# Nano_pi.net
KiCad netlist of a schematic drawn in Altium Designer
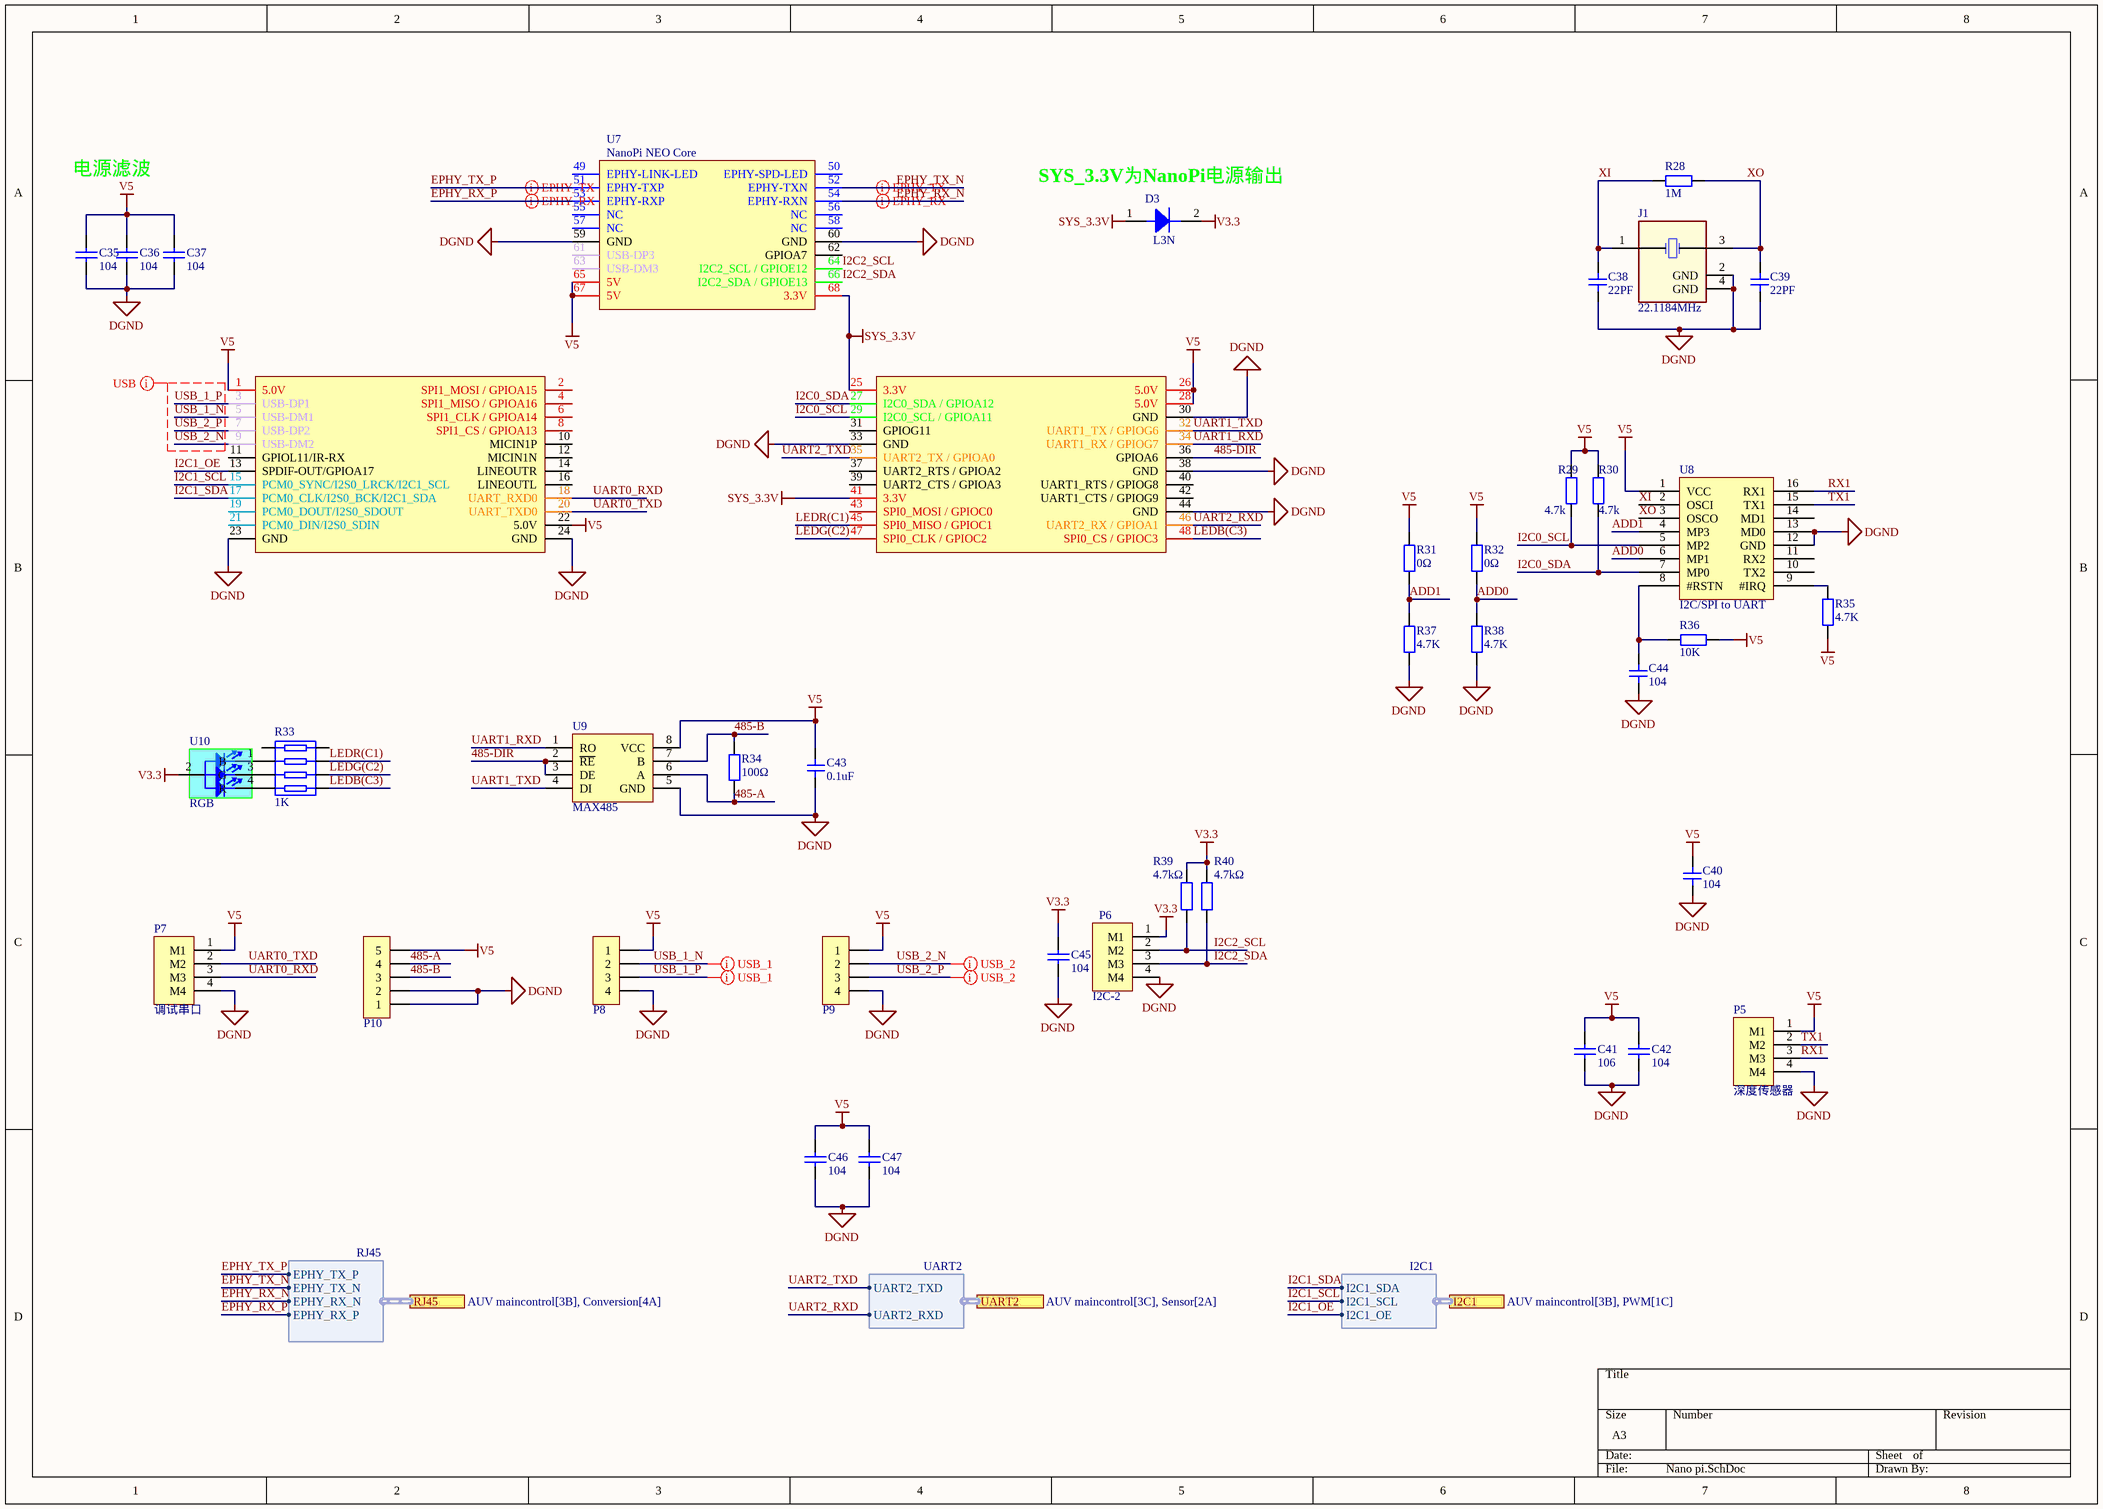
[diagram p0: Nano pi.SchDoc]

(export (version "E")
  (design (tool "Eeschema 10.0.6"))
  (components
    (comp (ref "C35")
      (value "104")
      (footprint "0603_C")
      (description "贴片电容")
      (libsource (lib "SFerret") (part "SMT_Cap"))
    )
    (comp (ref "C36")
      (value "104")
      (footprint "0603_C")
      (description "贴片电容")
      (libsource (lib "SFerret") (part "SMT_Cap"))
    )
    (comp (ref "C37")
      (value "104")
      (footprint "0603_C")
      (description "贴片电容")
      (libsource (lib "SFerret") (part "SMT_Cap"))
    )
    (comp (ref "C38")
      (value "22PF")
      (footprint "0603_C")
      (description "无极贴片电容")
      (libsource (lib "集大电协1.5") (part "Cap1"))
    )
    (comp (ref "C39")
      (value "22PF")
      (footprint "0603_C")
      (description "无极贴片电容")
      (libsource (lib "集大电协1.5") (part "Cap1"))
    )
    (comp (ref "C40")
      (value "104")
      (footprint "0603_C")
      (description "无极贴片电容")
      (libsource (lib "集大电协1.5") (part "Cap1"))
    )
    (comp (ref "C41")
      (value "106")
      (footprint "0603_C")
      (description "贴片电容")
      (libsource (lib "SFerret") (part "SMT_Cap"))
    )
    (comp (ref "C42")
      (value "104")
      (footprint "0603_C")
      (description "贴片电容")
      (libsource (lib "SFerret") (part "SMT_Cap"))
    )
    (comp (ref "C43")
      (value "0.1uF")
      (footprint "0603_C")
      (description "无极贴片电容")
      (libsource (lib "集大电协1.5") (part "Cap1"))
    )
    (comp (ref "C44")
      (value "104")
      (footprint "0603_C")
      (description "无极贴片电容")
      (libsource (lib "集大电协1.5") (part "Cap1"))
    )
    (comp (ref "C45")
      (value "104")
      (footprint "0603_C")
      (description "贴片电容")
      (libsource (lib "SFerret") (part "SMT_Cap"))
    )
    (comp (ref "C46")
      (value "104")
      (footprint "0603_C")
      (description "贴片电容")
      (libsource (lib "SFerret") (part "SMT_Cap"))
    )
    (comp (ref "C47")
      (value "104")
      (footprint "0603_C")
      (description "贴片电容")
      (libsource (lib "SFerret") (part "SMT_Cap"))
    )
    (comp (ref "D3")
      (value "L3N")
      (footprint "SOD-123")
      (description "二极管30V/2A")
      (libsource (lib "集大电协1.5") (part "Diode"))
    )
    (comp (ref "J1")
      (value "22.1184MHz")
      (footprint "SMD-3225_4P")
      (libsource (lib "SFerret") (part "Oscillator_SMT_4P"))
    )
    (comp (ref "P5")
      (value "深度传感器")
      (footprint "MX1.25S-4P")
      (description "4PIN")
      (libsource (lib "集大电协1.5") (part "接线端子-4PIN"))
    )
    (comp (ref "P6")
      (value "I2C-2")
      (footprint "MX1.25S-4P")
      (description "4PIN")
      (libsource (lib "集大电协1.5") (part "接线端子-4PIN"))
    )
    (comp (ref "P7")
      (value "调试串口")
      (footprint "MX1.25S-4P")
      (description "4PIN")
      (libsource (lib "集大电协1.5") (part "接线端子-4PIN"))
    )
    (comp (ref "P8")
      (value "HDR-1X4")
      (footprint "PH2.0-LS-4P")
      (description "4P接插件")
      (libsource (lib "5.3 - 接插件-脚距2.0") (part "Header 4"))
    )
    (comp (ref "P9")
      (value "HDR-1X4")
      (footprint "PH2.0-LS-4P")
      (description "4P接插件")
      (libsource (lib "5.3 - 接插件-脚距2.0") (part "Header 4"))
    )
    (comp (ref "P10")
      (value "HDR-1X5")
      (footprint "PH2.0-LS-5P")
      (description "5P接插件")
      (libsource (lib "5.3 - 接插件-脚距2.0") (part "Header 5"))
    )
    (comp (ref "R28")
      (value "1M")
      (footprint "0603R")
      (description "电阻")
      (libsource (lib "集大电协1.5") (part "Res"))
    )
    (comp (ref "R29")
      (value "4.7k")
      (footprint "0603R")
      (description "电阻")
      (libsource (lib "集大电协1.5") (part "Res"))
    )
    (comp (ref "R30")
      (value "4.7k")
      (footprint "0603R")
      (description "电阻")
      (libsource (lib "集大电协1.5") (part "Res"))
    )
    (comp (ref "R31")
      (value "0Ω")
      (footprint "0603R")
      (description "电阻")
      (libsource (lib "集大电协1.5") (part "Res"))
    )
    (comp (ref "R32")
      (value "0Ω")
      (footprint "0603R")
      (description "电阻")
      (libsource (lib "集大电协1.5") (part "Res"))
    )
    (comp (ref "R33")
      (value "1K")
      (footprint "res-4")
      (description "排阻")
      (libsource (lib "集大电协1.5") (part "Res-4"))
    )
    (comp (ref "R34")
      (value "100Ω")
      (footprint "0603R")
      (description "电阻")
      (libsource (lib "集大电协1.5") (part "Res"))
    )
    (comp (ref "R35")
      (value "4.7K")
      (footprint "0603R")
      (description "电阻")
      (libsource (lib "集大电协1.5") (part "Res"))
    )
    (comp (ref "R36")
      (value "10K")
      (footprint "0603R")
      (description "电阻")
      (libsource (lib "集大电协1.5") (part "Res"))
    )
    (comp (ref "R37")
      (value "4.7K")
      (footprint "0603R")
      (description "电阻")
      (libsource (lib "集大电协1.5") (part "Res"))
    )
    (comp (ref "R38")
      (value "4.7K")
      (footprint "0603R")
      (description "电阻")
      (libsource (lib "集大电协1.5") (part "Res"))
    )
    (comp (ref "R39")
      (value "4.7kΩ")
      (footprint "0603_R")
      (description "贴片电阻")
      (libsource (lib "SFerret") (part "SMT_Res"))
    )
    (comp (ref "R40")
      (value "4.7kΩ")
      (footprint "0603_R")
      (description "贴片电阻")
      (libsource (lib "SFerret") (part "SMT_Res"))
    )
    (comp (ref "U7")
      (value "NanoPi NEO Core")
      (footprint "NanoPi NEO Core(无引脚名)")
      (libsource (lib "集大电协1.5") (part "NanoPi NEO Core"))
    )
    (comp (ref "U8")
      (value "I2C/SPI to UART")
      (footprint "SOP65P780X195-16N")
      (libsource (lib "SFerret") (part "WK2132-ISSG"))
    )
    (comp (ref "U9") (value "MAX485") (footprint "SOP-8") (libsource (lib "集大电协1.5") (part "MAX485")))
    (comp (ref "U10") (value "RGB") (footprint "RGB-3528") (libsource (lib "集大电协1.1.2") (part "RGB")))
  )
  (nets
    (net (code "4") (name "/485-A") (class "Default")
      (node (ref "P10") (pin "4") (pinfunction "4_4") (pintype "passive"))
      (node (ref "R34") (pin "1") (pinfunction "1_1") (pintype "passive"))
      (node (ref "U9") (pin "6") (pinfunction "A_6") (pintype "passive"))
    )
    (net (code "5") (name "/485-B") (class "Default")
      (node (ref "P10") (pin "3") (pinfunction "3_3") (pintype "passive"))
      (node (ref "R34") (pin "2") (pinfunction "2_2") (pintype "passive"))
      (node (ref "U9") (pin "7") (pinfunction "B_7") (pintype "passive"))
    )
    (net (code "6") (name "/485-DIR") (class "Default")
      (node (ref "U7") (pin "36") (pinfunction "GPIOA6_36") (pintype "passive"))
      (node (ref "U9") (pin "2") (pinfunction "~{RE}_2") (pintype "passive"))
      (node (ref "U9") (pin "3") (pinfunction "DE_3") (pintype "passive"))
    )
    (net (code "8") (name "/ADD0") (class "Default")
      (node (ref "R32") (pin "1") (pinfunction "1_1") (pintype "passive"))
      (node (ref "R38") (pin "2") (pinfunction "2_2") (pintype "passive"))
      (node (ref "U8") (pin "6") (pinfunction "MP1_6") (pintype "passive"))
    )
    (net (code "9") (name "/ADD1") (class "Default")
      (node (ref "R31") (pin "1") (pinfunction "1_1") (pintype "passive"))
      (node (ref "R37") (pin "2") (pinfunction "2_2") (pintype "passive"))
      (node (ref "U8") (pin "4") (pinfunction "MP3_4") (pintype "passive"))
    )
    (net (code "10") (name "/EPHY_RX_N") (class "Default")
      (node (ref "U7") (pin "54") (pinfunction "EPHY-RXN_54") (pintype "passive"))
    )
    (net (code "11") (name "/EPHY_RX_P") (class "Default")
      (node (ref "U7") (pin "53") (pinfunction "EPHY-RXP_53") (pintype "passive"))
    )
    (net (code "12") (name "/EPHY_TX_N") (class "Default")
      (node (ref "U7") (pin "52") (pinfunction "EPHY-TXN_52") (pintype "passive"))
    )
    (net (code "13") (name "/EPHY_TX_P") (class "Default")
      (node (ref "U7") (pin "51") (pinfunction "EPHY-TXP_51") (pintype "passive"))
    )
    (net (code "14") (name "/I2C0_SCL") (class "Default")
      (node (ref "R29") (pin "1") (pinfunction "1_1") (pintype "passive"))
      (node (ref "U7") (pin "29") (pinfunction "I2C0_SCL_/_GPIOA11_29") (pintype "passive"))
      (node (ref "U8") (pin "5") (pinfunction "MP2_5") (pintype "passive"))
    )
    (net (code "15") (name "/I2C0_SDA") (class "Default")
      (node (ref "R30") (pin "1") (pinfunction "1_1") (pintype "passive"))
      (node (ref "U7") (pin "27") (pinfunction "I2C0_SDA_/_GPIOA12_27") (pintype "passive"))
      (node (ref "U8") (pin "7") (pinfunction "MP0_7") (pintype "passive"))
    )
    (net (code "16") (name "/I2C1_OE") (class "Default")
      (node (ref "U7") (pin "13") (pinfunction "SPDIF-OUT/GPIOA17_13") (pintype "passive"))
    )
    (net (code "17") (name "/I2C1_SCL") (class "Default")
      (node (ref "U7") (pin "15") (pinfunction "PCM0_SYNC/I2S0_LRCK/I2C1_SCL_15") (pintype "passive"))
    )
    (net (code "18") (name "/I2C1_SDA") (class "Default")
      (node (ref "U7") (pin "17") (pinfunction "PCM0_CLK/I2S0_BCK/I2C1_SDA_17") (pintype "passive"))
    )
    (net (code "19") (name "/I2C2_SCL") (class "Default")
      (node (ref "P6") (pin "2") (pinfunction "M2_2") (pintype "passive"))
      (node (ref "R39") (pin "1") (pinfunction "1_1") (pintype "passive"))
      (node (ref "U7") (pin "64") (pinfunction "I2C2_SCL_/_GPIOE12_64") (pintype "passive"))
    )
    (net (code "20") (name "/I2C2_SDA") (class "Default")
      (node (ref "P6") (pin "3") (pinfunction "M3_3") (pintype "passive"))
      (node (ref "R40") (pin "1") (pinfunction "1_1") (pintype "passive"))
      (node (ref "U7") (pin "66") (pinfunction "I2C2_SDA_/_GPIOE13_66") (pintype "passive"))
    )
    (net (code "21") (name "/LEDB(C3)") (class "Default")
      (node (ref "R33") (pin "5") (pinfunction "5_5") (pintype "passive"))
      (node (ref "U7") (pin "48") (pinfunction "SPI0_CS_/_GPIOC3_48") (pintype "passive"))
    )
    (net (code "22") (name "/LEDG(C2)") (class "Default")
      (node (ref "R33") (pin "6") (pinfunction "6_6") (pintype "passive"))
      (node (ref "U7") (pin "47") (pinfunction "SPI0_CLK_/_GPIOC2_47") (pintype "passive"))
    )
    (net (code "23") (name "/LEDR(C1)") (class "Default")
      (node (ref "R33") (pin "7") (pinfunction "7_7") (pintype "passive"))
      (node (ref "U7") (pin "45") (pinfunction "SPI0_MISO_/_GPIOC1_45") (pintype "passive"))
    )
    (net (code "24") (name "/RX1") (class "Default")
      (node (ref "P5") (pin "3") (pinfunction "M3_3") (pintype "passive"))
      (node (ref "U8") (pin "16") (pinfunction "RX1_16") (pintype "passive"))
    )
    (net (code "25") (name "/TX1") (class "Default")
      (node (ref "P5") (pin "2") (pinfunction "M2_2") (pintype "passive"))
      (node (ref "U8") (pin "15") (pinfunction "TX1_15") (pintype "passive"))
    )
    (net (code "26") (name "/UART0_RXD") (class "Default")
      (node (ref "P7") (pin "3") (pinfunction "M3_3") (pintype "passive"))
      (node (ref "U7") (pin "18") (pinfunction "UART_RXD0_18") (pintype "passive"))
    )
    (net (code "27") (name "/UART0_TXD") (class "Default")
      (node (ref "P7") (pin "2") (pinfunction "M2_2") (pintype "passive"))
      (node (ref "U7") (pin "20") (pinfunction "UART_TXD0_20") (pintype "passive"))
    )
    (net (code "28") (name "/UART1_RXD") (class "Default")
      (node (ref "U7") (pin "34") (pinfunction "UART1_RX_/_GPIOG7_34") (pintype "passive"))
      (node (ref "U9") (pin "1") (pinfunction "RO_1") (pintype "passive"))
    )
    (net (code "29") (name "/UART1_TXD") (class "Default")
      (node (ref "U7") (pin "32") (pinfunction "UART1_TX_/_GPIOG6_32") (pintype "passive"))
      (node (ref "U9") (pin "4") (pinfunction "DI_4") (pintype "passive"))
    )
    (net (code "30") (name "/UART2_RXD") (class "Default")
      (node (ref "U7") (pin "46") (pinfunction "UART2_RX_/_GPIOA1_46") (pintype "passive"))
    )
    (net (code "31") (name "/UART2_TXD") (class "Default")
      (node (ref "U7") (pin "35") (pinfunction "UART2_TX_/_GPIOA0_35") (pintype "passive"))
    )
    (net (code "32") (name "/USB_1_N") (class "Default")
      (node (ref "P8") (pin "2") (pinfunction "2_2") (pintype "passive"))
      (node (ref "U7") (pin "5") (pinfunction "USB-DM1_5") (pintype "passive"))
    )
    (net (code "33") (name "/USB_1_P") (class "Default")
      (node (ref "P8") (pin "3") (pinfunction "3_3") (pintype "passive"))
      (node (ref "U7") (pin "3") (pinfunction "USB-DP1_3") (pintype "passive"))
    )
    (net (code "34") (name "/USB_2_N") (class "Default")
      (node (ref "P9") (pin "2") (pinfunction "2_2") (pintype "passive"))
      (node (ref "U7") (pin "9") (pinfunction "USB-DM2_9") (pintype "passive"))
    )
    (net (code "35") (name "/USB_2_P") (class "Default")
      (node (ref "P9") (pin "3") (pinfunction "3_3") (pintype "passive"))
      (node (ref "U7") (pin "7") (pinfunction "USB-DP2_7") (pintype "passive"))
    )
    (net (code "36") (name "/XI") (class "Default")
      (node (ref "C38") (pin "1") (pinfunction "1_1") (pintype "passive"))
      (node (ref "J1") (pin "1") (pinfunction "OSC1_1") (pintype "passive"))
      (node (ref "R28") (pin "2") (pinfunction "2_2") (pintype "passive"))
      (node (ref "U8") (pin "2") (pinfunction "OSCI_2") (pintype "passive"))
    )
    (net (code "37") (name "/XO") (class "Default")
      (node (ref "C39") (pin "1") (pinfunction "1_1") (pintype "passive"))
      (node (ref "J1") (pin "3") (pinfunction "OSC2_3") (pintype "passive"))
      (node (ref "R28") (pin "1") (pinfunction "1_1") (pintype "passive"))
      (node (ref "U8") (pin "3") (pinfunction "OSCO_3") (pintype "passive"))
    )
    (net (code "41") (name "DGND") (class "Default")
      (node (ref "C35") (pin "1") (pinfunction "1_1") (pintype "passive"))
      (node (ref "C36") (pin "1") (pinfunction "1_1") (pintype "passive"))
      (node (ref "C37") (pin "1") (pinfunction "1_1") (pintype "passive"))
      (node (ref "C38") (pin "2") (pinfunction "2_2") (pintype "passive"))
      (node (ref "C39") (pin "2") (pinfunction "2_2") (pintype "passive"))
      (node (ref "C40") (pin "2") (pinfunction "2_2") (pintype "passive"))
      (node (ref "C41") (pin "1") (pinfunction "1_1") (pintype "passive"))
      (node (ref "C42") (pin "1") (pinfunction "1_1") (pintype "passive"))
      (node (ref "C43") (pin "1") (pinfunction "1_1") (pintype "passive"))
      (node (ref "C44") (pin "2") (pinfunction "2_2") (pintype "passive"))
      (node (ref "C45") (pin "1") (pinfunction "1_1") (pintype "passive"))
      (node (ref "C46") (pin "1") (pinfunction "1_1") (pintype "passive"))
      (node (ref "C47") (pin "1") (pinfunction "1_1") (pintype "passive"))
      (node (ref "J1") (pin "2") (pinfunction "GND_2") (pintype "passive"))
      (node (ref "J1") (pin "4") (pinfunction "GND_4") (pintype "passive"))
      (node (ref "P10") (pin "1") (pinfunction "1_1") (pintype "passive"))
      (node (ref "P10") (pin "2") (pinfunction "2_2") (pintype "passive"))
      (node (ref "P5") (pin "4") (pinfunction "M4_4") (pintype "passive"))
      (node (ref "P6") (pin "4") (pinfunction "M4_4") (pintype "passive"))
      (node (ref "P7") (pin "4") (pinfunction "M4_4") (pintype "passive"))
      (node (ref "P8") (pin "4") (pinfunction "4_4") (pintype "passive"))
      (node (ref "P9") (pin "4") (pinfunction "4_4") (pintype "passive"))
      (node (ref "R37") (pin "1") (pinfunction "1_1") (pintype "passive"))
      (node (ref "R38") (pin "1") (pinfunction "1_1") (pintype "passive"))
      (node (ref "U7") (pin "23") (pinfunction "GND_23") (pintype "passive"))
      (node (ref "U7") (pin "24") (pinfunction "GND_24") (pintype "passive"))
      (node (ref "U7") (pin "30") (pinfunction "GND_30") (pintype "passive"))
      (node (ref "U7") (pin "33") (pinfunction "GND_33") (pintype "passive"))
      (node (ref "U7") (pin "38") (pinfunction "GND_38") (pintype "passive"))
      (node (ref "U7") (pin "44") (pinfunction "GND_44") (pintype "passive"))
      (node (ref "U7") (pin "59") (pinfunction "GND_59") (pintype "passive"))
      (node (ref "U7") (pin "60") (pinfunction "GND_60") (pintype "passive"))
      (node (ref "U8") (pin "12") (pinfunction "GND_12") (pintype "passive"))
      (node (ref "U8") (pin "13") (pinfunction "MD0_13") (pintype "passive"))
      (node (ref "U9") (pin "5") (pinfunction "GND_5") (pintype "passive"))
    )
    (net (code "42") (name "Net-(U8-#IRQ)") (class "Default")
      (node (ref "R35") (pin "2") (pinfunction "2_2") (pintype "passive"))
      (node (ref "U8") (pin "9") (pinfunction "#IRQ_9") (pintype "passive"))
    )
    (net (code "43") (name "Net-(U8-#RSTN)") (class "Default")
      (node (ref "C44") (pin "1") (pinfunction "1_1") (pintype "passive"))
      (node (ref "R36") (pin "1") (pinfunction "1_1") (pintype "passive"))
      (node (ref "U8") (pin "8") (pinfunction "#RSTN_8") (pintype "passive"))
    )
    (net (code "44") (name "Net-(U10-B)") (class "Default")
      (node (ref "R33") (pin "2") (pinfunction "2_2") (pintype "passive"))
      (node (ref "U10") (pin "1") (pinfunction "B_1") (pintype "passive"))
    )
    (net (code "45") (name "Net-(U10-G)") (class "Default")
      (node (ref "R33") (pin "3") (pinfunction "3_3") (pintype "passive"))
      (node (ref "U10") (pin "3") (pinfunction "G_3") (pintype "passive"))
    )
    (net (code "46") (name "Net-(U10-R)") (class "Default")
      (node (ref "R33") (pin "4") (pinfunction "4_4") (pintype "passive"))
      (node (ref "U10") (pin "4") (pinfunction "R_4") (pintype "passive"))
    )
    (net (code "47") (name "SYS_3.3V") (class "Default")
      (node (ref "D3") (pin "1") (pintype "passive"))
      (node (ref "U7") (pin "25") (pinfunction "3.3V_25") (pintype "passive"))
      (node (ref "U7") (pin "41") (pinfunction "3.3V_41") (pintype "passive"))
      (node (ref "U7") (pin "68") (pinfunction "3.3V_68") (pintype "passive"))
    )
    (net (code "48") (name "V3.3") (class "Default")
      (node (ref "C45") (pin "2") (pinfunction "2_2") (pintype "passive"))
      (node (ref "D3") (pin "2") (pinfunction "2_2") (pintype "passive"))
      (node (ref "P6") (pin "1") (pinfunction "M1_1") (pintype "passive"))
      (node (ref "R39") (pin "2") (pinfunction "2_2") (pintype "passive"))
      (node (ref "R40") (pin "2") (pinfunction "2_2") (pintype "passive"))
      (node (ref "U10") (pin "2") (pinfunction "2_2") (pintype "passive"))
    )
    (net (code "49") (name "V5") (class "Default")
      (node (ref "C35") (pin "2") (pinfunction "2_2") (pintype "passive"))
      (node (ref "C36") (pin "2") (pinfunction "2_2") (pintype "passive"))
      (node (ref "C37") (pin "2") (pinfunction "2_2") (pintype "passive"))
      (node (ref "C40") (pin "1") (pinfunction "1_1") (pintype "passive"))
      (node (ref "C41") (pin "2") (pinfunction "2_2") (pintype "passive"))
      (node (ref "C42") (pin "2") (pinfunction "2_2") (pintype "passive"))
      (node (ref "C43") (pin "2") (pinfunction "2_2") (pintype "passive"))
      (node (ref "C46") (pin "2") (pinfunction "2_2") (pintype "passive"))
      (node (ref "C47") (pin "2") (pinfunction "2_2") (pintype "passive"))
      (node (ref "P10") (pin "5") (pinfunction "5_5") (pintype "passive"))
      (node (ref "P5") (pin "1") (pinfunction "M1_1") (pintype "passive"))
      (node (ref "P7") (pin "1") (pinfunction "M1_1") (pintype "passive"))
      (node (ref "P8") (pin "1") (pinfunction "1_1") (pintype "passive"))
      (node (ref "P9") (pin "1") (pinfunction "1_1") (pintype "passive"))
      (node (ref "R29") (pin "2") (pinfunction "2_2") (pintype "passive"))
      (node (ref "R30") (pin "2") (pinfunction "2_2") (pintype "passive"))
      (node (ref "R31") (pin "2") (pinfunction "2_2") (pintype "passive"))
      (node (ref "R32") (pin "2") (pinfunction "2_2") (pintype "passive"))
      (node (ref "R35") (pin "1") (pinfunction "1_1") (pintype "passive"))
      (node (ref "R36") (pin "2") (pinfunction "2_2") (pintype "passive"))
      (node (ref "U7") (pin "1") (pinfunction "5.0V_1") (pintype "passive"))
      (node (ref "U7") (pin "22") (pinfunction "5.0V_22") (pintype "passive"))
      (node (ref "U7") (pin "26") (pinfunction "5.0V_26") (pintype "passive"))
      (node (ref "U7") (pin "28") (pinfunction "5.0V_28") (pintype "passive"))
      (node (ref "U7") (pin "65") (pinfunction "5V_65") (pintype "passive"))
      (node (ref "U7") (pin "67") (pinfunction "5V_67") (pintype "passive"))
      (node (ref "U8") (pin "1") (pinfunction "VCC_1") (pintype "passive"))
      (node (ref "U9") (pin "8") (pinfunction "VCC_8") (pintype "passive"))
    )
    (net (code "50") (name "unconnected-(R33-Pad1)") (class "Default")
      (node (ref "R33") (pin "1") (pinfunction "1_1") (pintype "passive"))
    )
    (net (code "51") (name "unconnected-(R33-Pad8)") (class "Default")
      (node (ref "R33") (pin "8") (pinfunction "8_8") (pintype "passive"))
    )
    (net (code "52") (name "unconnected-(U7-EPHY-LINK-LED-Pad49)") (class "Default")
      (node (ref "U7") (pin "49") (pinfunction "EPHY-LINK-LED_49") (pintype "passive"))
    )
    (net (code "53") (name "unconnected-(U7-EPHY-SPD-LED-Pad50)") (class "Default")
      (node (ref "U7") (pin "50") (pinfunction "EPHY-SPD-LED_50") (pintype "passive"))
    )
    (net (code "54") (name "unconnected-(U7-GPIOA7-Pad62)") (class "Default")
      (node (ref "U7") (pin "62") (pinfunction "GPIOA7_62") (pintype "passive"))
    )
    (net (code "55") (name "unconnected-(U7-GPIOG11-Pad31)") (class "Default")
      (node (ref "U7") (pin "31") (pinfunction "GPIOG11_31") (pintype "passive"))
    )
    (net (code "56") (name "unconnected-(U7-GPIOL11{slash}IR-RX-Pad11)") (class "Default")
      (node (ref "U7") (pin "11") (pinfunction "GPIOL11/IR-RX_11") (pintype "passive"))
    )
    (net (code "57") (name "unconnected-(U7-LINEOUTL-Pad16)") (class "Default")
      (node (ref "U7") (pin "16") (pinfunction "LINEOUTL_16") (pintype "passive"))
    )
    (net (code "58") (name "unconnected-(U7-LINEOUTR-Pad14)") (class "Default")
      (node (ref "U7") (pin "14") (pinfunction "LINEOUTR_14") (pintype "passive"))
    )
    (net (code "59") (name "unconnected-(U7-MICIN1N-Pad12)") (class "Default")
      (node (ref "U7") (pin "12") (pinfunction "MICIN1N_12") (pintype "passive"))
    )
    (net (code "60") (name "unconnected-(U7-MICIN1P-Pad10)") (class "Default")
      (node (ref "U7") (pin "10") (pinfunction "MICIN1P_10") (pintype "passive"))
    )
    (net (code "61") (name "unconnected-(U7-NC-Pad55)") (class "Default")
      (node (ref "U7") (pin "55") (pinfunction "NC_55") (pintype "passive"))
    )
    (net (code "62") (name "unconnected-(U7-NC-Pad56)") (class "Default")
      (node (ref "U7") (pin "56") (pinfunction "NC_56") (pintype "passive"))
    )
    (net (code "63") (name "unconnected-(U7-NC-Pad57)") (class "Default")
      (node (ref "U7") (pin "57") (pinfunction "NC_57") (pintype "passive"))
    )
    (net (code "64") (name "unconnected-(U7-NC-Pad58)") (class "Default")
      (node (ref "U7") (pin "58") (pinfunction "NC_58") (pintype "passive"))
    )
    (net (code "65") (name "unconnected-(U7-PCM0_DIN{slash}I2S0_SDIN-Pad21)") (class "Default")
      (node (ref "U7") (pin "21") (pinfunction "PCM0_DIN/I2S0_SDIN_21") (pintype "passive"))
    )
    (net (code "66") (name "unconnected-(U7-PCM0_DOUT{slash}I2S0_SDOUT-Pad19)") (class "Default")
      (node (ref "U7") (pin "19") (pinfunction "PCM0_DOUT/I2S0_SDOUT_19") (pintype "passive"))
    )
    (net (code "67") (name "unconnected-(U7-SPI0_MOSI_{slash}_GPIOC0-Pad43)") (class "Default")
      (node (ref "U7") (pin "43") (pinfunction "SPI0_MOSI_/_GPIOC0_43") (pintype "passive"))
    )
    (net (code "68") (name "unconnected-(U7-SPI1_CLK_{slash}_GPIOA14-Pad6)") (class "Default")
      (node (ref "U7") (pin "6") (pinfunction "SPI1_CLK_/_GPIOA14_6") (pintype "passive"))
    )
    (net (code "69") (name "unconnected-(U7-SPI1_CS_{slash}_GPIOA13-Pad8)") (class "Default")
      (node (ref "U7") (pin "8") (pinfunction "SPI1_CS_/_GPIOA13_8") (pintype "passive"))
    )
    (net (code "70") (name "unconnected-(U7-SPI1_MISO_{slash}_GPIOA16-Pad4)") (class "Default")
      (node (ref "U7") (pin "4") (pinfunction "SPI1_MISO_/_GPIOA16_4") (pintype "passive"))
    )
    (net (code "71") (name "unconnected-(U7-SPI1_MOSI_{slash}_GPIOA15-Pad2)") (class "Default")
      (node (ref "U7") (pin "2") (pinfunction "SPI1_MOSI_/_GPIOA15_2") (pintype "passive"))
    )
    (net (code "72") (name "unconnected-(U7-UART1_CTS_{slash}_GPIOG9-Pad42)") (class "Default")
      (node (ref "U7") (pin "42") (pinfunction "UART1_CTS_/_GPIOG9_42") (pintype "passive"))
    )
    (net (code "73") (name "unconnected-(U7-UART1_RTS_{slash}_GPIOG8-Pad40)") (class "Default")
      (node (ref "U7") (pin "40") (pinfunction "UART1_RTS_/_GPIOG8_40") (pintype "passive"))
    )
    (net (code "74") (name "unconnected-(U7-UART2_CTS_{slash}_GPIOA3-Pad39)") (class "Default")
      (node (ref "U7") (pin "39") (pinfunction "UART2_CTS_/_GPIOA3_39") (pintype "passive"))
    )
    (net (code "75") (name "unconnected-(U7-UART2_RTS_{slash}_GPIOA2-Pad37)") (class "Default")
      (node (ref "U7") (pin "37") (pinfunction "UART2_RTS_/_GPIOA2_37") (pintype "passive"))
    )
    (net (code "76") (name "unconnected-(U7-USB-DM3-Pad63)") (class "Default")
      (node (ref "U7") (pin "63") (pinfunction "USB-DM3_63") (pintype "passive"))
    )
    (net (code "77") (name "unconnected-(U7-USB-DP3-Pad61)") (class "Default")
      (node (ref "U7") (pin "61") (pinfunction "USB-DP3_61") (pintype "passive"))
    )
    (net (code "78") (name "unconnected-(U8-MD1-Pad14)") (class "Default")
      (node (ref "U8") (pin "14") (pinfunction "MD1_14") (pintype "passive"))
    )
    (net (code "79") (name "unconnected-(U8-RX2-Pad11)") (class "Default")
      (node (ref "U8") (pin "11") (pinfunction "RX2_11") (pintype "passive"))
    )
    (net (code "80") (name "unconnected-(U8-TX2-Pad10)") (class "Default")
      (node (ref "U8") (pin "10") (pinfunction "TX2_10") (pintype "passive"))
    )
  )
)
